# Schematic.net
KiCad netlist of a schematic drawn in EAGLE
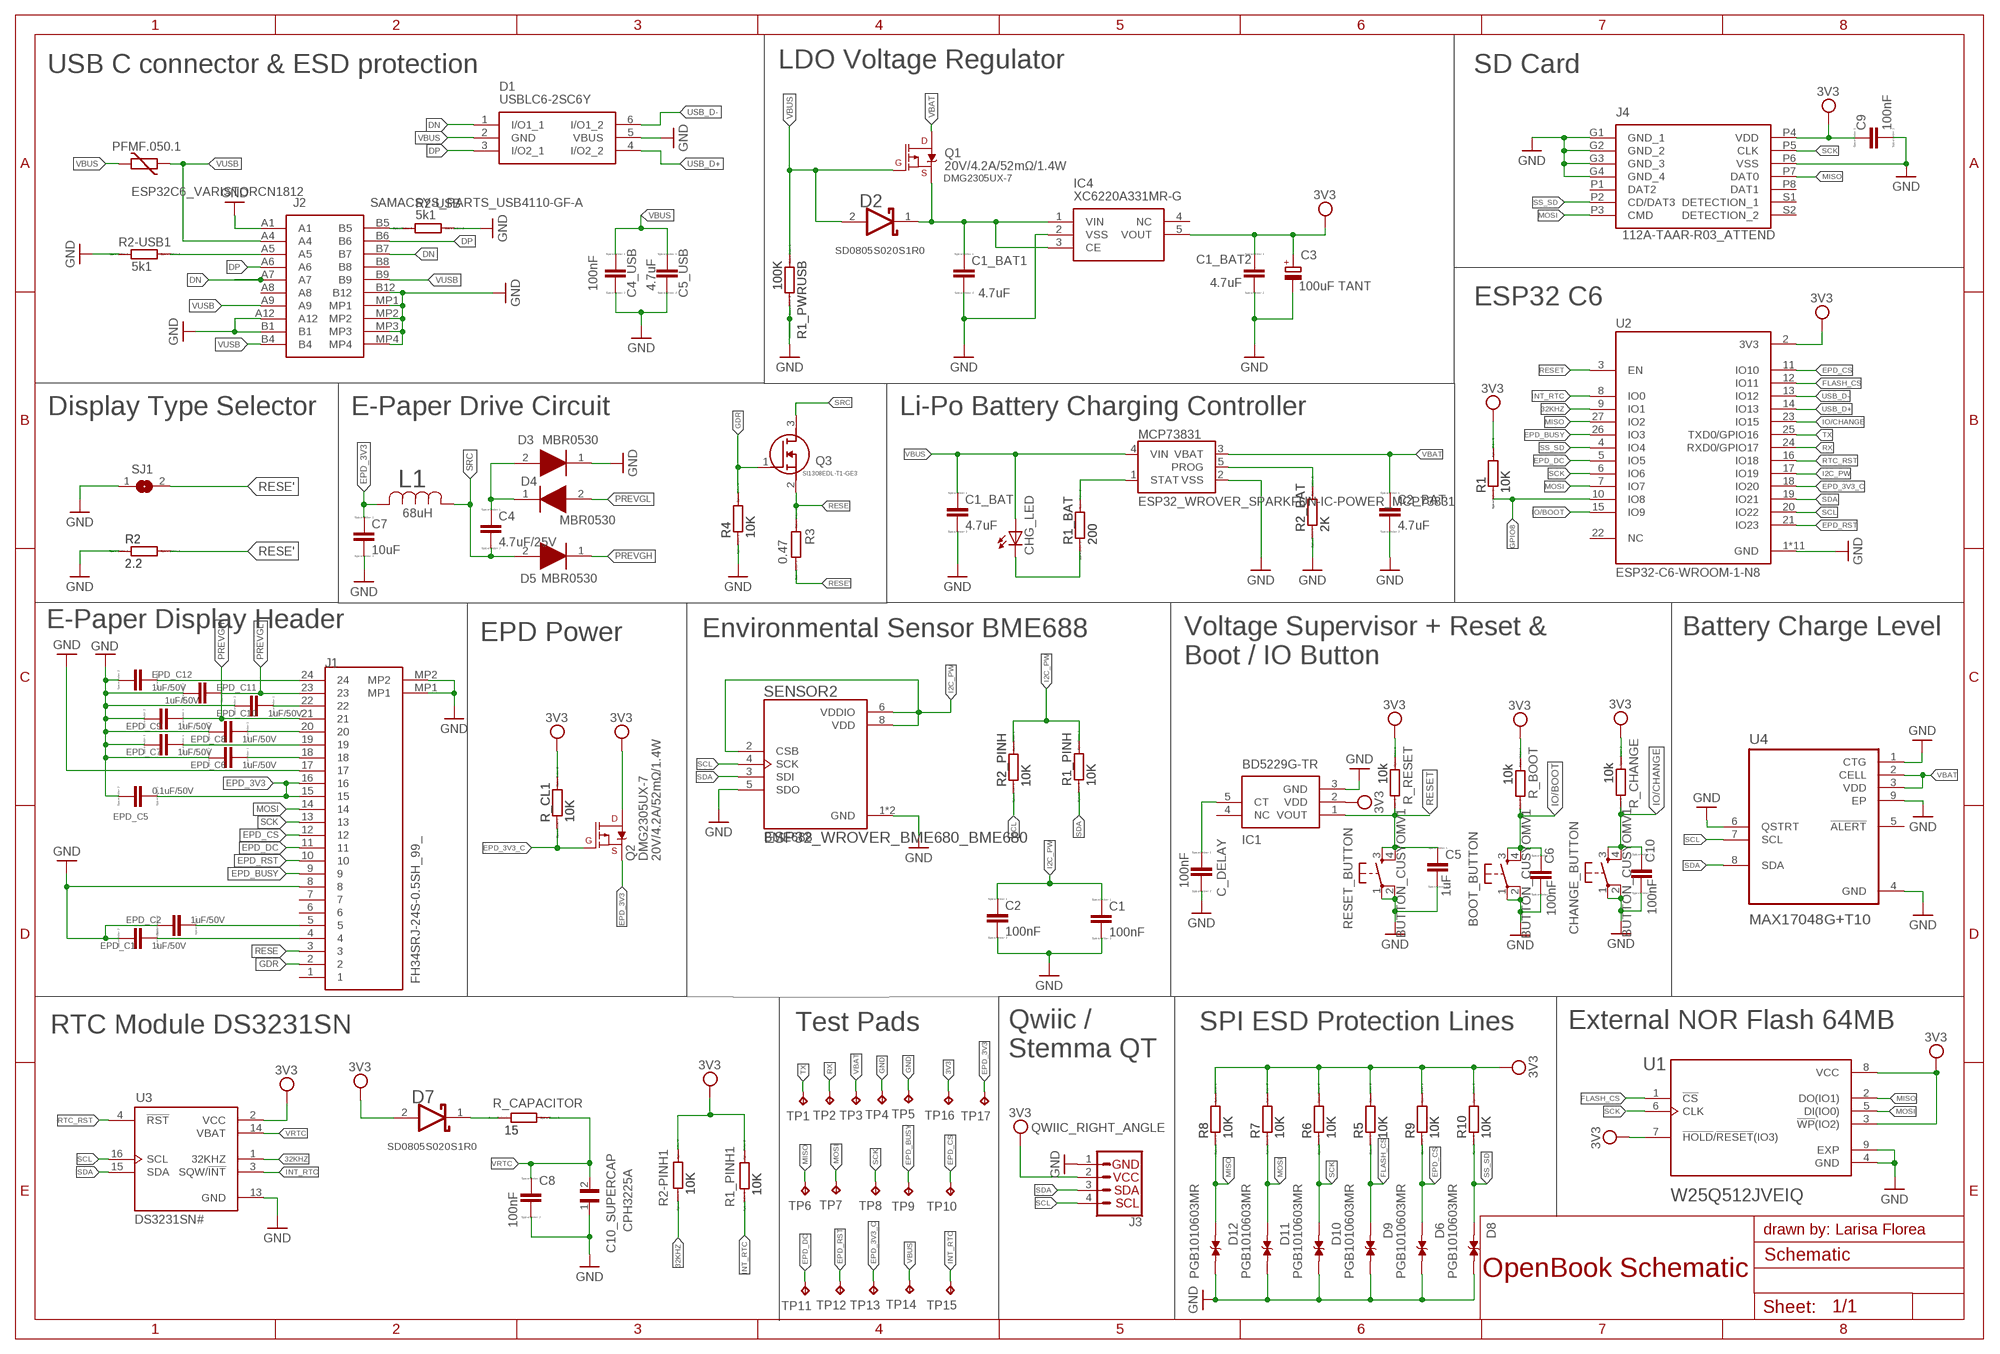
[diagram p0: schematic, sheet 1]

(export (version "E")
  (design (tool "Eeschema 10.0.6"))
  (components
    (comp (ref "BOOT_BUTTON")
      (value "BUTTON_CUSYOMV1")
      (footprint "eagle-import:MYBUTTON")
      (libsource (lib "eagle-import") (part "BUTTON_CUSYOMV1"))
    )
    (comp (ref "C1")
      (value "100nF")
      (footprint "eagle-import:EAGLE-LTSPICE_C0402")
      (libsource (lib "eagle-import") (part "EAGLE-LTSPICE_CC0402"))
    )
    (comp (ref "C1_BAT")
      (value "4.7uF")
      (footprint "eagle-import:EAGLE-LTSPICE_C0402")
      (libsource (lib "eagle-import") (part "EAGLE-LTSPICE_CC0402"))
    )
    (comp (ref "C1_BAT1")
      (value "4.7uF")
      (footprint "eagle-import:ESP32_WROVER_EAGLE-LTSPICE_C0402")
      (libsource (lib "eagle-import") (part "ESP32_WROVER_EAGLE-LTSPICE_CC0402"))
    )
    (comp (ref "C1_BAT2")
      (value "4.7uF")
      (footprint "eagle-import:ESP32_WROVER_EAGLE-LTSPICE_C0402")
      (libsource (lib "eagle-import") (part "ESP32_WROVER_EAGLE-LTSPICE_CC0402"))
    )
    (comp (ref "C2")
      (value "100nF")
      (footprint "eagle-import:EAGLE-LTSPICE_C0402")
      (libsource (lib "eagle-import") (part "EAGLE-LTSPICE_CC0402"))
    )
    (comp (ref "C2_BAT")
      (value "4.7uF")
      (footprint "eagle-import:EAGLE-LTSPICE_C0402")
      (libsource (lib "eagle-import") (part "EAGLE-LTSPICE_CC0402"))
    )
    (comp (ref "C3")
      (value "100uF TANT")
      (footprint "eagle-import:RCL_CT3528")
      (libsource (lib "eagle-import") (part "RCL_CPOL-EUCT3528"))
    )
    (comp (ref "C4")
      (value "4.7uF/25V")
      (footprint "eagle-import:ESP32_WROVER_EAGLE-LTSPICE_C0402")
      (libsource (lib "eagle-import") (part "ESP32_WROVER_EAGLE-LTSPICE_CC0402"))
    )
    (comp (ref "C4_USB")
      (value "100nF")
      (footprint "eagle-import:ESP32_WROVER_EAGLE-LTSPICE_C0402")
      (libsource (lib "eagle-import") (part "ESP32_WROVER_EAGLE-LTSPICE_CC0402"))
    )
    (comp (ref "C5")
      (value "1uF")
      (footprint "eagle-import:EAGLE-LTSPICE_C0402")
      (libsource (lib "eagle-import") (part "EAGLE-LTSPICE_CC0402"))
    )
    (comp (ref "C5_USB")
      (value "4.7uF")
      (footprint "eagle-import:ESP32_WROVER_EAGLE-LTSPICE_C0402")
      (libsource (lib "eagle-import") (part "ESP32_WROVER_EAGLE-LTSPICE_CC0402"))
    )
    (comp (ref "C6")
      (value "100nF")
      (footprint "eagle-import:EAGLE-LTSPICE_C0402")
      (libsource (lib "eagle-import") (part "EAGLE-LTSPICE_CC0402"))
    )
    (comp (ref "C7")
      (value "10uF")
      (footprint "eagle-import:ESP32_WROVER_EAGLE-LTSPICE_C0402")
      (libsource (lib "eagle-import") (part "ESP32_WROVER_EAGLE-LTSPICE_CC0402"))
    )
    (comp (ref "C8")
      (value "100nF")
      (footprint "eagle-import:EAGLE-LTSPICE_C0402")
      (libsource (lib "eagle-import") (part "EAGLE-LTSPICE_CC0402"))
    )
    (comp (ref "C9")
      (value "100nF")
      (footprint "eagle-import:EAGLE-LTSPICE_C0402")
      (libsource (lib "eagle-import") (part "EAGLE-LTSPICE_CC0402"))
    )
    (comp (ref "C10")
      (value "100nF")
      (footprint "eagle-import:EAGLE-LTSPICE_C0402")
      (libsource (lib "eagle-import") (part "EAGLE-LTSPICE_CC0402"))
    )
    (comp (ref "C10_SUPERCAP")
      (value "CPH3225A")
      (footprint "eagle-import:CAPCP3225X100N")
      (fields (field (name "MF") "Seiko Instruments"))
      (libsource (lib "eagle-import") (part "CPH3225A"))
    )
    (comp (ref "CHANGE_BUTTON")
      (value "BUTTON_CUSYOMV1")
      (footprint "eagle-import:MYBUTTON")
      (libsource (lib "eagle-import") (part "BUTTON_CUSYOMV1"))
    )
    (comp (ref "CHG_LED")
      (value "ADAFRUIT_LEDCHIP-LED0603")
      (footprint "eagle-import:ADAFRUIT_CHIP-LED0603")
      (libsource (lib "eagle-import") (part "ADAFRUIT_LEDCHIP-LED0603"))
    )
    (comp (ref "C_DELAY")
      (value "100nF")
      (footprint "eagle-import:EAGLE-LTSPICE_C0402")
      (libsource (lib "eagle-import") (part "EAGLE-LTSPICE_CC0402"))
    )
    (comp (ref "D1")
      (value "USBLC6-2SC6Y")
      (footprint "eagle-import:SOT95P280X145-6N")
      (fields (field (name "MF") "STMicroelectronics"))
      (libsource (lib "eagle-import") (part "USBLC6-2SC6Y"))
    )
    (comp (ref "D2")
      (value "ESP32_WROVER_AVX---SD0805S020S1R0_AVX_SD0805S020S1R0_0_0AVX_SD0805S020S1R0_0_0")
      (footprint "eagle-import:ESP32_WROVER_AVX---SD0805S020S1R0_AVX_SD0805S020S1R0_0")
      (fields
        (field (name "DIGIKEY_PART_NUMBER") "478-7800-1-ND")
        (field (name "MF") "AVX")
        (field (name "MOUSER_PART_NUMBER") "581-SD0805S020S1R0")
      )
      (libsource (lib "eagle-import") (part "ESP32_WROVER_AVX---SD0805S020S1R0_AVX_SD0805S020S1R0_0_0AVX_SD0805S020S1R0_0_0"))
    )
    (comp (ref "D3")
      (value "MBR0530")
      (footprint "eagle-import:SOD3716X135N")
      (fields (field (name "MF") "ON Semiconductor"))
      (libsource (lib "eagle-import") (part "MBR0530"))
    )
    (comp (ref "D4")
      (value "MBR0530")
      (footprint "eagle-import:SOD3716X135N")
      (fields (field (name "MF") "ON Semiconductor"))
      (libsource (lib "eagle-import") (part "MBR0530"))
    )
    (comp (ref "D5")
      (value "MBR0530")
      (footprint "eagle-import:SOD3716X135N")
      (fields (field (name "MF") "ON Semiconductor"))
      (libsource (lib "eagle-import") (part "MBR0530"))
    )
    (comp (ref "D6")
      (value "PGB1010603MR")
      (footprint "eagle-import:DIOC1608X36N")
      (fields (field (name "MF") "Littelfuse Inc."))
      (libsource (lib "eagle-import") (part "PGB1010603MR"))
    )
    (comp (ref "D7")
      (value "ESP32_WROVER_AVX---SD0805S020S1R0_AVX_SD0805S020S1R0_0_0AVX_SD0805S020S1R0_0_0")
      (footprint "eagle-import:ESP32_WROVER_AVX---SD0805S020S1R0_AVX_SD0805S020S1R0_0")
      (fields
        (field (name "DIGIKEY_PART_NUMBER") "478-7800-1-ND")
        (field (name "MF") "AVX")
        (field (name "MOUSER_PART_NUMBER") "581-SD0805S020S1R0")
      )
      (libsource (lib "eagle-import") (part "ESP32_WROVER_AVX---SD0805S020S1R0_AVX_SD0805S020S1R0_0_0AVX_SD0805S020S1R0_0_0"))
    )
    (comp (ref "D8")
      (value "PGB1010603MR")
      (footprint "eagle-import:DIOC1608X36N")
      (fields (field (name "MF") "Littelfuse Inc."))
      (libsource (lib "eagle-import") (part "PGB1010603MR"))
    )
    (comp (ref "D9")
      (value "PGB1010603MR")
      (footprint "eagle-import:DIOC1608X36N")
      (fields (field (name "MF") "Littelfuse Inc."))
      (libsource (lib "eagle-import") (part "PGB1010603MR"))
    )
    (comp (ref "D10")
      (value "PGB1010603MR")
      (footprint "eagle-import:DIOC1608X36N")
      (fields (field (name "MF") "Littelfuse Inc."))
      (libsource (lib "eagle-import") (part "PGB1010603MR"))
    )
    (comp (ref "D11")
      (value "PGB1010603MR")
      (footprint "eagle-import:DIOC1608X36N")
      (fields (field (name "MF") "Littelfuse Inc."))
      (libsource (lib "eagle-import") (part "PGB1010603MR"))
    )
    (comp (ref "D12")
      (value "PGB1010603MR")
      (footprint "eagle-import:DIOC1608X36N")
      (fields (field (name "MF") "Littelfuse Inc."))
      (libsource (lib "eagle-import") (part "PGB1010603MR"))
    )
    (comp (ref "EPD_C1")
      (value "1uF/50V")
      (footprint "eagle-import:ESP32_WROVER_EAGLE-LTSPICE_C0402")
      (libsource (lib "eagle-import") (part "DeskAssistant v19 v1_vf.GPlzlSHfQFaX3NeFr78fQQ_ESP32_WROVER_EAGLE-LTSPICE_CC0402"))
    )
    (comp (ref "EPD_C2")
      (value "1uF/50V")
      (footprint "eagle-import:ESP32_WROVER_EAGLE-LTSPICE_C0402")
      (libsource (lib "eagle-import") (part "DeskAssistant v19 v1_vf.GPlzlSHfQFaX3NeFr78fQQ_ESP32_WROVER_EAGLE-LTSPICE_CC0402"))
    )
    (comp (ref "EPD_C5")
      (value "0.1uF/50V")
      (footprint "eagle-import:ESP32_WROVER_EAGLE-LTSPICE_C0402")
      (libsource (lib "eagle-import") (part "DeskAssistant v19 v1_vf.GPlzlSHfQFaX3NeFr78fQQ_ESP32_WROVER_EAGLE-LTSPICE_CC0402"))
    )
    (comp (ref "EPD_C6")
      (value "1uF/50V")
      (footprint "eagle-import:ESP32_WROVER_EAGLE-LTSPICE_C0402")
      (libsource (lib "eagle-import") (part "DeskAssistant v19 v1_vf.GPlzlSHfQFaX3NeFr78fQQ_ESP32_WROVER_EAGLE-LTSPICE_CC0402"))
    )
    (comp (ref "EPD_C7")
      (value "1uF/50V")
      (footprint "eagle-import:ESP32_WROVER_EAGLE-LTSPICE_C0402")
      (libsource (lib "eagle-import") (part "DeskAssistant v19 v1_vf.GPlzlSHfQFaX3NeFr78fQQ_ESP32_WROVER_EAGLE-LTSPICE_CC0402"))
    )
    (comp (ref "EPD_C8")
      (value "1uF/50V")
      (footprint "eagle-import:ESP32_WROVER_EAGLE-LTSPICE_C0402")
      (libsource (lib "eagle-import") (part "DeskAssistant v19 v1_vf.GPlzlSHfQFaX3NeFr78fQQ_ESP32_WROVER_EAGLE-LTSPICE_CC0402"))
    )
    (comp (ref "EPD_C9")
      (value "1uF/50V")
      (footprint "eagle-import:ESP32_WROVER_EAGLE-LTSPICE_C0402")
      (libsource (lib "eagle-import") (part "DeskAssistant v19 v1_vf.GPlzlSHfQFaX3NeFr78fQQ_ESP32_WROVER_EAGLE-LTSPICE_CC0402"))
    )
    (comp (ref "EPD_C10")
      (value "1uF/50V")
      (footprint "eagle-import:ESP32_WROVER_EAGLE-LTSPICE_C0402")
      (libsource (lib "eagle-import") (part "DeskAssistant v19 v1_vf.GPlzlSHfQFaX3NeFr78fQQ_ESP32_WROVER_EAGLE-LTSPICE_CC0402"))
    )
    (comp (ref "EPD_C11")
      (value "1uF/50V")
      (footprint "eagle-import:ESP32_WROVER_EAGLE-LTSPICE_C0402")
      (libsource (lib "eagle-import") (part "DeskAssistant v19 v1_vf.GPlzlSHfQFaX3NeFr78fQQ_ESP32_WROVER_EAGLE-LTSPICE_CC0402"))
    )
    (comp (ref "EPD_C12")
      (value "1uF/50V")
      (footprint "eagle-import:ESP32_WROVER_EAGLE-LTSPICE_C0402")
      (libsource (lib "eagle-import") (part "DeskAssistant v19 v1_vf.GPlzlSHfQFaX3NeFr78fQQ_ESP32_WROVER_EAGLE-LTSPICE_CC0402"))
    )
    (comp (ref "IC1")
      (value "BD5229G-TR")
      (footprint "eagle-import:SOT95P280X125-5N")
      (fields (field (name "MOUSER_PART_NUMBER") "755-BD5229G-TR"))
      (libsource (lib "eagle-import") (part "BD5229G-TR"))
    )
    (comp (ref "IC4")
      (value "XC6220A331MR-G")
      (footprint "eagle-import:SOT95P280X120-5N")
      (fields (field (name "MOUSER_PART_NUMBER") "865-XC6220A331MR-G"))
      (libsource (lib "eagle-import") (part "XC6220A331MR-G"))
    )
    (comp (ref "J1")
      (value "FH34SRJ-24S-0.5SH_99_")
      (footprint "eagle-import:FH34SRJ24S05SH99")
      (fields
        (field (name "MANUFACTURER_PART_NUMBER") "FH34SRJ-24S-0.5SH(99)")
        (field (name "MOUSER_PART_NUMBER") "798-FH34SRJ24S05SH99")
      )
      (libsource (lib "eagle-import") (part "FH34SRJ-24S-0.5SH_99_"))
    )
    (comp (ref "J2")
      (value "SAMACSYS_PARTS_USB4110-GF-A")
      (footprint "eagle-import:SAMACSYS_PARTS_USB4110GFA")
      (fields
        (field (name "MANUFACTURER_PART_NUMBER") "USB4110-GF-A")
        (field (name "MOUSER_PART_NUMBER") "640-USB4110-GF-A")
      )
      (libsource (lib "eagle-import") (part "SAMACSYS_PARTS_USB4110-GF-A"))
    )
    (comp (ref "J3")
      (value "QWIIC_RIGHT_ANGLE")
      (footprint "eagle-import:JST04_1MM_RA")
      (libsource (lib "eagle-import") (part "QWIIC_CONNECTORJS-1MM"))
    )
    (comp (ref "J4")
      (value "112A-TAAR-R03_ATTEND")
      (footprint "eagle-import:112ATAARR03ATTEND")
      (fields (field (name "MANUFACTURER_PART_NUMBER") "112A-TAAR-R03 ATTEND"))
      (libsource (lib "eagle-import") (part "112A-TAAR-R03_ATTEND"))
    )
    (comp (ref "L1")
      (value "744043680IND_4828-WE-TPC_WRE")
      (footprint "eagle-import:IND_4828-WE-TPC_WRE")
      (fields
        (field (name "MANUFACTURER_PART_NUMBER") "744043680")
        (field (name "68UH") "68uH")
        (field (name "COPYRIGHT") "Copyright (C) 2024 Ultra Librarian. All rights reserved.")
      )
      (libsource (lib "eagle-import") (part "744043680IND_4828-WE-TPC_WRE"))
    )
    (comp (ref "MCP73831")
      (value "ESP32_WROVER_SPARKFUN-IC-POWER_MCP73831")
      (footprint "eagle-import:ESP32_WROVER_SPARKFUN-IC-POWER_SOT23-5")
      (libsource (lib "eagle-import") (part "ESP32_WROVER_SPARKFUN-IC-POWER_MCP73831"))
    )
    (comp (ref "PFMF.050.1")
      (value "ESP32C6_VARISTORCN1812")
      (footprint "eagle-import:ESP32C6_VARISTOR_CT_CN1812")
      (libsource (lib "eagle-import") (part "ESP32C6_VARISTORCN1812"))
    )
    (comp (ref "Q1")
      (value "20V/4.2A/52mΩ/1.4W")
      (footprint "eagle-import:ESP32_WROVER_SPARKFUN-DISCRETESEMI_SOT23-3")
      (libsource (lib "eagle-import") (part "ESP32_WROVER_SPARKFUN-DISCRETESEMI_MOSFET_PCH-DMG2305UX-7"))
    )
    (comp (ref "Q2")
      (value "20V/4.2A/52mΩ/1.4W")
      (footprint "eagle-import:ESP32_WROVER_SPARKFUN-DISCRETESEMI_SOT23-3")
      (libsource (lib "eagle-import") (part "ESP32_WROVER_SPARKFUN-DISCRETESEMI_MOSFET_PCH-DMG2305UX-7"))
    )
    (comp (ref "Q3")
      (value "SI1308EDL-T1-GE3")
      (footprint "eagle-import:SOT65P210X110-3N")
      (fields (field (name "MF") "Vishay Siliconix"))
      (libsource (lib "eagle-import") (part "SI1308EDL-T1-GE3"))
    )
    (comp (ref "R1")
      (value "10K")
      (footprint "eagle-import:ESP32_WROVER_EAGLE-LTSPICE_R0402")
      (libsource (lib "eagle-import") (part "ESP32_WROVER_EAGLE-LTSPICE_RR0402"))
    )
    (comp (ref "R1_BAT")
      (value "200")
      (footprint "eagle-import:ESP32_WROVER_EAGLE-LTSPICE_R0402")
      (libsource (lib "eagle-import") (part "ESP32_WROVER_EAGLE-LTSPICE_RR0402"))
    )
    (comp (ref "R1_PINH")
      (value "10K")
      (footprint "eagle-import:ESP32_WROVER_EAGLE-LTSPICE_R0402")
      (libsource (lib "eagle-import") (part "ESP32_WROVER_EAGLE-LTSPICE_RR0402"))
    )
    (comp (ref "R1_PINH1")
      (value "10K")
      (footprint "eagle-import:ESP32_WROVER_EAGLE-LTSPICE_R0402")
      (libsource (lib "eagle-import") (part "ESP32_WROVER_EAGLE-LTSPICE_RR0402"))
    )
    (comp (ref "R1_PWRUSB")
      (value "100K")
      (footprint "eagle-import:ESP32_WROVER_EAGLE-LTSPICE_R0402")
      (libsource (lib "eagle-import") (part "ESP32_WROVER_EAGLE-LTSPICE_RR0402"))
    )
    (comp (ref "R2")
      (value "2.2")
      (footprint "eagle-import:ESP32_WROVER_EAGLE-LTSPICE_R0402")
      (libsource (lib "eagle-import") (part "ESP32_WROVER_EAGLE-LTSPICE_RR0402"))
    )
    (comp (ref "R2-PINH1")
      (value "10K")
      (footprint "eagle-import:ESP32_WROVER_EAGLE-LTSPICE_R0402")
      (libsource (lib "eagle-import") (part "ESP32_WROVER_EAGLE-LTSPICE_RR0402"))
    )
    (comp (ref "R2-USB")
      (value "5k1")
      (footprint "eagle-import:ESP32_WROVER_EAGLE-LTSPICE_R0402")
      (libsource (lib "eagle-import") (part "ESP32_WROVER_EAGLE-LTSPICE_RR0402"))
    )
    (comp (ref "R2-USB1")
      (value "5k1")
      (footprint "eagle-import:ESP32_WROVER_EAGLE-LTSPICE_R0402")
      (libsource (lib "eagle-import") (part "ESP32_WROVER_EAGLE-LTSPICE_RR0402"))
    )
    (comp (ref "R2_BAT")
      (value "2K")
      (footprint "eagle-import:ESP32_WROVER_EAGLE-LTSPICE_R0402")
      (libsource (lib "eagle-import") (part "ESP32_WROVER_EAGLE-LTSPICE_RR0402"))
    )
    (comp (ref "R2_PINH")
      (value "10K")
      (footprint "eagle-import:ESP32_WROVER_EAGLE-LTSPICE_R0402")
      (libsource (lib "eagle-import") (part "ESP32_WROVER_EAGLE-LTSPICE_RR0402"))
    )
    (comp (ref "R3")
      (value "0.47")
      (footprint "eagle-import:ESP32_WROVER_EAGLE-LTSPICE_R0402")
      (libsource (lib "eagle-import") (part "ESP32_WROVER_EAGLE-LTSPICE_RR0402"))
    )
    (comp (ref "R4")
      (value "10K")
      (footprint "eagle-import:ESP32_WROVER_EAGLE-LTSPICE_R0402")
      (libsource (lib "eagle-import") (part "ESP32_WROVER_EAGLE-LTSPICE_RR0402"))
    )
    (comp (ref "R5")
      (value "10K")
      (footprint "eagle-import:ESP32_WROVER_EAGLE-LTSPICE_R0402")
      (libsource (lib "eagle-import") (part "DeskAssistant v19 v1_vf.GPlzlSHfQFaX3NeFr78fQQ_ESP32_WROVER_EAGLE-LTSPICE_RR0402"))
    )
    (comp (ref "R6")
      (value "10K")
      (footprint "eagle-import:ESP32_WROVER_EAGLE-LTSPICE_R0402")
      (libsource (lib "eagle-import") (part "DeskAssistant v19 v1_vf.GPlzlSHfQFaX3NeFr78fQQ_ESP32_WROVER_EAGLE-LTSPICE_RR0402"))
    )
    (comp (ref "R7")
      (value "10K")
      (footprint "eagle-import:ESP32_WROVER_EAGLE-LTSPICE_R0402")
      (libsource (lib "eagle-import") (part "DeskAssistant v19 v1_vf.GPlzlSHfQFaX3NeFr78fQQ_ESP32_WROVER_EAGLE-LTSPICE_RR0402"))
    )
    (comp (ref "R8")
      (value "10K")
      (footprint "eagle-import:ESP32_WROVER_EAGLE-LTSPICE_R0402")
      (libsource (lib "eagle-import") (part "DeskAssistant v19 v1_vf.GPlzlSHfQFaX3NeFr78fQQ_ESP32_WROVER_EAGLE-LTSPICE_RR0402"))
    )
    (comp (ref "R9")
      (value "10K")
      (footprint "eagle-import:ESP32_WROVER_EAGLE-LTSPICE_R0402")
      (libsource (lib "eagle-import") (part "DeskAssistant v19 v1_vf.GPlzlSHfQFaX3NeFr78fQQ_ESP32_WROVER_EAGLE-LTSPICE_RR0402"))
    )
    (comp (ref "R10")
      (value "10K")
      (footprint "eagle-import:ESP32_WROVER_EAGLE-LTSPICE_R0402")
      (libsource (lib "eagle-import") (part "DeskAssistant v19 v1_vf.GPlzlSHfQFaX3NeFr78fQQ_ESP32_WROVER_EAGLE-LTSPICE_RR0402"))
    )
    (comp (ref "RESET_BUTTON")
      (value "BUTTON_CUSYOMV1")
      (footprint "eagle-import:MYBUTTON")
      (libsource (lib "eagle-import") (part "BUTTON_CUSYOMV1"))
    )
    (comp (ref "R_BOOT")
      (value "10k")
      (footprint "eagle-import:ESP32_WROVER_EAGLE-LTSPICE_R0402")
      (libsource (lib "eagle-import") (part "ESP32_WROVER_EAGLE-LTSPICE_RR0402"))
    )
    (comp (ref "R_CAPACITOR")
      (value "15")
      (footprint "eagle-import:ESP32_WROVER_EAGLE-LTSPICE_R0402")
      (libsource (lib "eagle-import") (part "ESP32_WROVER_EAGLE-LTSPICE_RR0402"))
    )
    (comp (ref "R_CHANGE")
      (value "10k")
      (footprint "eagle-import:ESP32_WROVER_EAGLE-LTSPICE_R0402")
      (libsource (lib "eagle-import") (part "ESP32_WROVER_EAGLE-LTSPICE_RR0402"))
    )
    (comp (ref "R_CL1")
      (value "10K")
      (footprint "eagle-import:ESP32_WROVER_EAGLE-LTSPICE_R0402")
      (libsource (lib "eagle-import") (part "ESP32_WROVER_EAGLE-LTSPICE_RR0402"))
    )
    (comp (ref "R_RESET")
      (value "10k")
      (footprint "eagle-import:ESP32_WROVER_EAGLE-LTSPICE_R0402")
      (libsource (lib "eagle-import") (part "ESP32_WROVER_EAGLE-LTSPICE_RR0402"))
    )
    (comp (ref "SENSOR2")
      (value "ESP32_WROVER_BME680_BME680")
      (footprint "eagle-import:ESP32_WROVER_BME680_PSON80P300X300X100-8N")
      (fields (field (name "MF") "Bosch Sensortec") (field (name "MP") "BME680"))
      (libsource (lib "eagle-import") (part "ESP32_WROVER_BME680_BME680"))
    )
    (comp (ref "SJ1") (value "SJ") (footprint "eagle-import:SJ") (libsource (lib "eagle-import") (part "SJ")))
    (comp (ref "TP1")
      (value "TPTP20R")
      (footprint "eagle-import:TP20R")
      (libsource (lib "eagle-import") (part "TPTP20R"))
    )
    (comp (ref "TP2")
      (value "TPTP20R")
      (footprint "eagle-import:TP20R")
      (libsource (lib "eagle-import") (part "TPTP20R"))
    )
    (comp (ref "TP3")
      (value "TPTP20R")
      (footprint "eagle-import:TP20R")
      (libsource (lib "eagle-import") (part "TPTP20R"))
    )
    (comp (ref "TP4")
      (value "TPTP20R")
      (footprint "eagle-import:TP20R")
      (libsource (lib "eagle-import") (part "TPTP20R"))
    )
    (comp (ref "TP5")
      (value "TPTP20R")
      (footprint "eagle-import:TP20R")
      (libsource (lib "eagle-import") (part "TPTP20R"))
    )
    (comp (ref "TP6")
      (value "TPTP20R")
      (footprint "eagle-import:TP20R")
      (libsource (lib "eagle-import") (part "TPTP20R"))
    )
    (comp (ref "TP7")
      (value "TPTP20R")
      (footprint "eagle-import:TP20R")
      (libsource (lib "eagle-import") (part "TPTP20R"))
    )
    (comp (ref "TP8")
      (value "TPTP20R")
      (footprint "eagle-import:TP20R")
      (libsource (lib "eagle-import") (part "TPTP20R"))
    )
    (comp (ref "TP9")
      (value "TPTP20R")
      (footprint "eagle-import:TP20R")
      (libsource (lib "eagle-import") (part "TPTP20R"))
    )
    (comp (ref "TP10")
      (value "TPTP20R")
      (footprint "eagle-import:TP20R")
      (libsource (lib "eagle-import") (part "TPTP20R"))
    )
    (comp (ref "TP11")
      (value "TPTP20R")
      (footprint "eagle-import:TP20R")
      (libsource (lib "eagle-import") (part "TPTP20R"))
    )
    (comp (ref "TP12")
      (value "TPTP20R")
      (footprint "eagle-import:TP20R")
      (libsource (lib "eagle-import") (part "TPTP20R"))
    )
    (comp (ref "TP13")
      (value "TPTP20R")
      (footprint "eagle-import:TP20R")
      (libsource (lib "eagle-import") (part "TPTP20R"))
    )
    (comp (ref "TP14")
      (value "TPTP20R")
      (footprint "eagle-import:TP20R")
      (libsource (lib "eagle-import") (part "TPTP20R"))
    )
    (comp (ref "TP15")
      (value "TPTP20R")
      (footprint "eagle-import:TP20R")
      (libsource (lib "eagle-import") (part "TPTP20R"))
    )
    (comp (ref "TP16")
      (value "TPTP20R")
      (footprint "eagle-import:TP20R")
      (libsource (lib "eagle-import") (part "TPTP20R"))
    )
    (comp (ref "TP17")
      (value "TPTP20R")
      (footprint "eagle-import:TP20R")
      (libsource (lib "eagle-import") (part "TPTP20R"))
    )
    (comp (ref "U1")
      (value "W25Q512JVEIQ")
      (footprint "eagle-import:SON127P600X800X80-9N")
      (fields (field (name "MF") "Winbond Electronics"))
      (libsource (lib "eagle-import") (part "W25Q512JVEIQ"))
    )
    (comp (ref "U2")
      (value "ESP32-C6-WROOM-1-N8")
      (footprint "eagle-import:XCVR_ESP32-C6-WROOM-1-N8")
      (fields (field (name "MF") "Espressif Systems"))
      (libsource (lib "eagle-import") (part "ESP32-C6-WROOM-1-N8"))
    )
    (comp (ref "U3")
      (value "DS3231SN#")
      (footprint "eagle-import:SOIC127P1032X265-16N")
      (fields (field (name "MF") "Analog Devices"))
      (libsource (lib "eagle-import") (part "DS3231SN#"))
    )
    (comp (ref "U4")
      (value "MAX17048G+T10")
      (footprint "eagle-import:SON50P200X200X80-9N")
      (fields (field (name "MF") "Analog Devices"))
      (libsource (lib "eagle-import") (part "MAX17048G+T10"))
    )
  )
  (nets
    (net (code "1") (name "3V3") (class "Default")
      (node (ref "C1_BAT2") (pin "1") (pinfunction "1_1") (pintype "passive"))
      (node (ref "C3") (pin "+") (pinfunction "+_+") (pintype "passive"))
      (node (ref "C9") (pin "1") (pinfunction "1_1") (pintype "passive"))
      (node (ref "D7") (pin "2") (pinfunction "ANODE_2") (pintype "bidirectional"))
      (node (ref "IC1") (pin "2") (pinfunction "VDD_2") (pintype "bidirectional"))
      (node (ref "IC4") (pin "5") (pinfunction "VOUT_5") (pintype "bidirectional"))
      (node (ref "J3") (pin "2") (pinfunction "2_2") (pintype "power_in"))
      (node (ref "J4") (pin "P4") (pinfunction "VDD_P4") (pintype "bidirectional"))
      (node (ref "Q2") (pin "3") (pinfunction "D_3") (pintype "bidirectional"))
      (node (ref "R1") (pin "2") (pinfunction "2_2") (pintype "passive"))
      (node (ref "R10") (pin "2") (pinfunction "2_2") (pintype "passive"))
      (node (ref "R1_PINH1") (pin "2") (pinfunction "2_2") (pintype "passive"))
      (node (ref "R2-PINH1") (pin "2") (pinfunction "2_2") (pintype "passive"))
      (node (ref "R5") (pin "2") (pinfunction "2_2") (pintype "passive"))
      (node (ref "R6") (pin "2") (pinfunction "2_2") (pintype "passive"))
      (node (ref "R7") (pin "2") (pinfunction "2_2") (pintype "passive"))
      (node (ref "R8") (pin "2") (pinfunction "2_2") (pintype "passive"))
      (node (ref "R9") (pin "2") (pinfunction "2_2") (pintype "passive"))
      (node (ref "R_BOOT") (pin "1") (pinfunction "1_1") (pintype "passive"))
      (node (ref "R_CHANGE") (pin "1") (pinfunction "1_1") (pintype "passive"))
      (node (ref "R_CL1") (pin "2") (pinfunction "2_2") (pintype "passive"))
      (node (ref "R_RESET") (pin "1") (pinfunction "1_1") (pintype "passive"))
      (node (ref "TP16") (pin "TP") (pinfunction "TP_TP") (pintype "input"))
      (node (ref "U1") (pin "3") (pinfunction "~{WP}(IO2)_3") (pintype "bidirectional"))
      (node (ref "U1") (pin "7") (pinfunction "~{HOLD}/~{RESET}(IO3)_7") (pintype "bidirectional"))
      (node (ref "U1") (pin "8") (pinfunction "VCC_8") (pintype "power_in"))
      (node (ref "U2") (pin "2") (pinfunction "3V3_2") (pintype "power_in"))
      (node (ref "U3") (pin "2") (pinfunction "VCC_2") (pintype "power_in"))
    )
    (net (code "2") (name "32KHZ") (class "Default")
      (node (ref "R2-PINH1") (pin "1") (pinfunction "1_1") (pintype "passive"))
      (node (ref "U2") (pin "9") (pinfunction "IO1_9") (pintype "bidirectional"))
      (node (ref "U3") (pin "1") (pinfunction "32KHZ_1") (pintype "output"))
    )
    (net (code "3") (name "DN") (class "Default")
      (node (ref "D1") (pin "1") (pinfunction "I/O1_1_1") (pintype "bidirectional"))
      (node (ref "J2") (pin "A7") (pinfunction "A7_A7") (pintype "bidirectional"))
      (node (ref "J2") (pin "B7") (pinfunction "B7_B7") (pintype "bidirectional"))
    )
    (net (code "4") (name "DP") (class "Default")
      (node (ref "D1") (pin "3") (pinfunction "I/O2_1_3") (pintype "bidirectional"))
      (node (ref "J2") (pin "A6") (pinfunction "A6_A6") (pintype "bidirectional"))
      (node (ref "J2") (pin "B6") (pinfunction "B6_B6") (pintype "bidirectional"))
    )
    (net (code "5") (name "EPD_3V3") (class "Default")
      (node (ref "C7") (pin "1") (pinfunction "1_1") (pintype "passive"))
      (node (ref "EPD_C5") (pin "1") (pinfunction "1_1") (pintype "passive"))
      (node (ref "J1") (pin "15") (pinfunction "15_15") (pintype "bidirectional"))
      (node (ref "J1") (pin "16") (pinfunction "16_16") (pintype "bidirectional"))
      (node (ref "L1") (pin "2") (pinfunction "2_2") (pintype "passive"))
      (node (ref "Q2") (pin "2") (pinfunction "S_2") (pintype "bidirectional"))
      (node (ref "TP17") (pin "TP") (pinfunction "TP_TP") (pintype "input"))
    )
    (net (code "6") (name "EPD_3V3_C") (class "Default")
      (node (ref "Q2") (pin "1") (pinfunction "G_1") (pintype "bidirectional"))
      (node (ref "R_CL1") (pin "1") (pinfunction "1_1") (pintype "passive"))
      (node (ref "TP13") (pin "TP") (pinfunction "TP_TP") (pintype "input"))
      (node (ref "U2") (pin "18") (pinfunction "IO20_18") (pintype "bidirectional"))
    )
    (net (code "7") (name "EPD_BUSY") (class "Default")
      (node (ref "J1") (pin "9") (pinfunction "9_9") (pintype "bidirectional"))
      (node (ref "TP9") (pin "TP") (pinfunction "TP_TP") (pintype "input"))
      (node (ref "U2") (pin "26") (pinfunction "IO3_26") (pintype "bidirectional"))
    )
    (net (code "8") (name "EPD_CS") (class "Default")
      (node (ref "D6") (pin "1") (pinfunction "1_1") (pintype "passive"))
      (node (ref "J1") (pin "12") (pinfunction "12_12") (pintype "bidirectional"))
      (node (ref "R9") (pin "1") (pinfunction "1_1") (pintype "passive"))
      (node (ref "TP10") (pin "TP") (pinfunction "TP_TP") (pintype "input"))
      (node (ref "U2") (pin "11") (pinfunction "IO10_11") (pintype "bidirectional"))
    )
    (net (code "9") (name "EPD_DC") (class "Default")
      (node (ref "J1") (pin "11") (pinfunction "11_11") (pintype "bidirectional"))
      (node (ref "TP11") (pin "TP") (pinfunction "TP_TP") (pintype "input"))
      (node (ref "U2") (pin "5") (pinfunction "IO5_5") (pintype "bidirectional"))
    )
    (net (code "10") (name "EPD_RST") (class "Default")
      (node (ref "J1") (pin "10") (pinfunction "10_10") (pintype "bidirectional"))
      (node (ref "TP12") (pin "TP") (pinfunction "TP_TP") (pintype "input"))
      (node (ref "U2") (pin "21") (pinfunction "IO23_21") (pintype "bidirectional"))
    )
    (net (code "11") (name "FLASH_CS") (class "Default")
      (node (ref "D9") (pin "1") (pinfunction "1_1") (pintype "passive"))
      (node (ref "R5") (pin "1") (pinfunction "1_1") (pintype "passive"))
      (node (ref "U1") (pin "1") (pinfunction "~{CS}_1") (pintype "input"))
      (node (ref "U2") (pin "12") (pinfunction "IO11_12") (pintype "bidirectional"))
    )
    (net (code "12") (name "GDR") (class "Default")
      (node (ref "J1") (pin "2") (pinfunction "2_2") (pintype "bidirectional"))
      (node (ref "Q3") (pin "1") (pinfunction "G_1") (pintype "bidirectional"))
      (node (ref "R4") (pin "2") (pinfunction "2_2") (pintype "passive"))
    )
    (net (code "13") (name "GND") (class "Default")
      (node (ref "BOOT_BUTTON") (pin "1") (pinfunction "1_1") (pintype "passive"))
      (node (ref "BOOT_BUTTON") (pin "2") (pinfunction "2_2") (pintype "passive"))
      (node (ref "C1") (pin "2") (pinfunction "2_2") (pintype "passive"))
      (node (ref "C10") (pin "2") (pinfunction "2_2") (pintype "passive"))
      (node (ref "C10_SUPERCAP") (pin "1") (pinfunction "1_1") (pintype "passive"))
      (node (ref "C1_BAT") (pin "2") (pinfunction "2_2") (pintype "passive"))
      (node (ref "C1_BAT1") (pin "2") (pinfunction "2_2") (pintype "passive"))
      (node (ref "C1_BAT2") (pin "2") (pinfunction "2_2") (pintype "passive"))
      (node (ref "C2") (pin "2") (pinfunction "2_2") (pintype "passive"))
      (node (ref "C2_BAT") (pin "2") (pinfunction "2_2") (pintype "passive"))
      (node (ref "C3") (pin "-") (pinfunction "-_-") (pintype "passive"))
      (node (ref "C4_USB") (pin "2") (pinfunction "2_2") (pintype "passive"))
      (node (ref "C5") (pin "2") (pinfunction "2_2") (pintype "passive"))
      (node (ref "C5_USB") (pin "2") (pinfunction "2_2") (pintype "passive"))
      (node (ref "C6") (pin "2") (pinfunction "2_2") (pintype "passive"))
      (node (ref "C7") (pin "2") (pinfunction "2_2") (pintype "passive"))
      (node (ref "C8") (pin "2") (pinfunction "2_2") (pintype "passive"))
      (node (ref "C9") (pin "2") (pinfunction "2_2") (pintype "passive"))
      (node (ref "CHANGE_BUTTON") (pin "1") (pinfunction "1_1") (pintype "passive"))
      (node (ref "CHANGE_BUTTON") (pin "2") (pinfunction "2_2") (pintype "passive"))
      (node (ref "C_DELAY") (pin "2") (pinfunction "2_2") (pintype "passive"))
      (node (ref "D1") (pin "5") (pinfunction "VBUS_5") (pintype "bidirectional"))
      (node (ref "D10") (pin "2") (pinfunction "2_2") (pintype "passive"))
      (node (ref "D11") (pin "2") (pinfunction "2_2") (pintype "passive"))
      (node (ref "D12") (pin "2") (pinfunction "2_2") (pintype "passive"))
      (node (ref "D3") (pin "1") (pinfunction "K_1") (pintype "bidirectional"))
      (node (ref "D6") (pin "2") (pinfunction "2_2") (pintype "passive"))
      (node (ref "D8") (pin "2") (pinfunction "2_2") (pintype "passive"))
      (node (ref "D9") (pin "2") (pinfunction "2_2") (pintype "passive"))
      (node (ref "EPD_C1") (pin "2") (pinfunction "2_2") (pintype "passive"))
      (node (ref "EPD_C10") (pin "2") (pinfunction "2_2") (pintype "passive"))
      (node (ref "EPD_C11") (pin "2") (pinfunction "2_2") (pintype "passive"))
      (node (ref "EPD_C12") (pin "2") (pinfunction "2_2") (pintype "passive"))
      (node (ref "EPD_C2") (pin "2") (pinfunction "2_2") (pintype "passive"))
      (node (ref "EPD_C5") (pin "2") (pinfunction "2_2") (pintype "passive"))
      (node (ref "EPD_C6") (pin "2") (pinfunction "2_2") (pintype "passive"))
      (node (ref "EPD_C7") (pin "2") (pinfunction "2_2") (pintype "passive"))
      (node (ref "EPD_C8") (pin "2") (pinfunction "2_2") (pintype "passive"))
      (node (ref "EPD_C9") (pin "2") (pinfunction "2_2") (pintype "passive"))
      (node (ref "IC1") (pin "3") (pinfunction "GND_3") (pintype "bidirectional"))
      (node (ref "IC4") (pin "2") (pinfunction "VSS_2") (pintype "bidirectional"))
      (node (ref "J1") (pin "17") (pinfunction "17_17") (pintype "bidirectional"))
      (node (ref "J1") (pin "8") (pinfunction "8_8") (pintype "bidirectional"))
      (node (ref "J1") (pin "MP1") (pinfunction "MP1_MP1") (pintype "bidirectional"))
      (node (ref "J1") (pin "MP2") (pinfunction "MP2_MP2") (pintype "bidirectional"))
      (node (ref "J2") (pin "A1") (pinfunction "A1_A1") (pintype "bidirectional"))
      (node (ref "J2") (pin "A12") (pinfunction "A12_A12") (pintype "bidirectional"))
      (node (ref "J2") (pin "B1") (pinfunction "B1_B1") (pintype "bidirectional"))
      (node (ref "J2") (pin "B12") (pinfunction "B12_B12") (pintype "bidirectional"))
      (node (ref "J2") (pin "MP1") (pinfunction "MP1_MP1") (pintype "bidirectional"))
      (node (ref "J2") (pin "MP2") (pinfunction "MP2_MP2") (pintype "bidirectional"))
      (node (ref "J2") (pin "MP3") (pinfunction "MP3_MP3") (pintype "bidirectional"))
      (node (ref "J2") (pin "MP4") (pinfunction "MP4_MP4") (pintype "bidirectional"))
      (node (ref "J3") (pin "1") (pinfunction "1_1") (pintype "power_in"))
      (node (ref "J4") (pin "G1") (pinfunction "GND_1_G1") (pintype "bidirectional"))
      (node (ref "J4") (pin "G2") (pinfunction "GND_2_G2") (pintype "bidirectional"))
      (node (ref "J4") (pin "G3") (pinfunction "GND_3_G3") (pintype "bidirectional"))
      (node (ref "J4") (pin "G4") (pinfunction "GND_4_G4") (pintype "bidirectional"))
      (node (ref "J4") (pin "P6") (pinfunction "VSS_P6") (pintype "bidirectional"))
      (node (ref "MCP73831") (pin "2") (pinfunction "VSS_2") (pintype "power_in"))
      (node (ref "R1_PWRUSB") (pin "2") (pinfunction "2_2") (pintype "passive"))
      (node (ref "R2") (pin "1") (pinfunction "1_1") (pintype "passive"))
      (node (ref "R2-USB") (pin "2") (pinfunction "2_2") (pintype "passive"))
      (node (ref "R2-USB1") (pin "1") (pinfunction "1_1") (pintype "passive"))
      (node (ref "R2_BAT") (pin "1") (pinfunction "1_1") (pintype "passive"))
      (node (ref "R4") (pin "1") (pinfunction "1_1") (pintype "passive"))
      (node (ref "RESET_BUTTON") (pin "1") (pinfunction "1_1") (pintype "passive"))
      (node (ref "RESET_BUTTON") (pin "2") (pinfunction "2_2") (pintype "passive"))
      (node (ref "SENSOR2") (pin "1") (pinfunction "GND_1") (pintype "power_in"))
      (node (ref "SENSOR2") (pin "5") (pinfunction "SDO_5") (pintype "bidirectional"))
      (node (ref "SENSOR2") (pin "7") (pinfunction "GND_7") (pintype "power_in"))
      (node (ref "SJ1") (pin "1") (pinfunction "1_1") (pintype "passive"))
      (node (ref "TP4") (pin "TP") (pinfunction "TP_TP") (pintype "input"))
      (node (ref "TP5") (pin "TP") (pinfunction "TP_TP") (pintype "input"))
      (node (ref "U1") (pin "4") (pinfunction "GND_4") (pintype "power_in"))
      (node (ref "U1") (pin "9") (pinfunction "EXP_9") (pintype "passive"))
      (node (ref "U2") (pin "1") (pinfunction "GND_1") (pintype "power_in"))
      (node (ref "U2") (pin "28") (pinfunction "GND_28") (pintype "power_in"))
      (node (ref "U2") (pin "29_1") (pinfunction "GND_29_1") (pintype "power_in"))
      (node (ref "U2") (pin "29_2") (pinfunction "GND_29_2") (pintype "power_in"))
      (node (ref "U2") (pin "29_3") (pinfunction "GND_29_3") (pintype "power_in"))
      (node (ref "U2") (pin "29_4") (pinfunction "GND_29_4") (pintype "power_in"))
      (node (ref "U2") (pin "29_5") (pinfunction "GND_29_5") (pintype "power_in"))
      (node (ref "U2") (pin "29_6") (pinfunction "GND_29_6") (pintype "power_in"))
      (node (ref "U2") (pin "29_7") (pinfunction "GND_29_7") (pintype "power_in"))
      (node (ref "U2") (pin "29_8") (pinfunction "GND_29_8") (pintype "power_in"))
      (node (ref "U2") (pin "29_9") (pinfunction "GND_29_9") (pintype "power_in"))
      (node (ref "U3") (pin "13") (pinfunction "GND_13") (pintype "power_in"))
      (node (ref "U4") (pin "1") (pinfunction "CTG_1") (pintype "power_in"))
      (node (ref "U4") (pin "4") (pinfunction "GND_4") (pintype "power_in"))
      (node (ref "U4") (pin "6") (pinfunction "QSTRT_6") (pintype "input"))
      (node (ref "U4") (pin "9") (pinfunction "EP_9") (pintype "power_in"))
    )
    (net (code "14") (name "GPIO8") (class "Default")
      (node (ref "R1") (pin "1") (pinfunction "1_1") (pintype "passive"))
      (node (ref "U2") (pin "10") (pinfunction "IO8_10") (pintype "bidirectional"))
    )
    (net (code "15") (name "I2C_PW") (class "Default")
      (node (ref "C1") (pin "1") (pinfunction "1_1") (pintype "passive"))
      (node (ref "C2") (pin "1") (pinfunction "1_1") (pintype "passive"))
      (node (ref "R1_PINH") (pin "2") (pinfunction "2_2") (pintype "passive"))
      (node (ref "R2_PINH") (pin "2") (pinfunction "2_2") (pintype "passive"))
      (node (ref "SENSOR2") (pin "2") (pinfunction "CSB_2") (pintype "input"))
      (node (ref "SENSOR2") (pin "6") (pinfunction "VDDIO_6") (pintype "power_in"))
      (node (ref "SENSOR2") (pin "8") (pinfunction "VDD_8") (pintype "power_in"))
      (node (ref "U2") (pin "17") (pinfunction "IO19_17") (pintype "bidirectional"))
    )
    (net (code "16") (name "INT_RTC") (class "Default")
      (node (ref "R1_PINH1") (pin "1") (pinfunction "1_1") (pintype "passive"))
      (node (ref "TP15") (pin "TP") (pinfunction "TP_TP") (pintype "input"))
      (node (ref "U2") (pin "8") (pinfunction "IO0_8") (pintype "bidirectional"))
      (node (ref "U3") (pin "3") (pinfunction "SQW/~{INT}_3") (pintype "output"))
    )
    (net (code "17") (name "IO{slash}BOOT") (class "Default")
      (node (ref "BOOT_BUTTON") (pin "3") (pinfunction "3_3") (pintype "passive"))
      (node (ref "BOOT_BUTTON") (pin "4") (pinfunction "4_4") (pintype "passive"))
      (node (ref "C6") (pin "1") (pinfunction "1_1") (pintype "passive"))
      (node (ref "R_BOOT") (pin "2") (pinfunction "2_2") (pintype "passive"))
      (node (ref "U2") (pin "15") (pinfunction "IO9_15") (pintype "bidirectional"))
    )
    (net (code "18") (name "IO{slash}CHANGE") (class "Default")
      (node (ref "C10") (pin "1") (pinfunction "1_1") (pintype "passive"))
      (node (ref "CHANGE_BUTTON") (pin "3") (pinfunction "3_3") (pintype "passive"))
      (node (ref "CHANGE_BUTTON") (pin "4") (pinfunction "4_4") (pintype "passive"))
      (node (ref "R_CHANGE") (pin "2") (pinfunction "2_2") (pintype "passive"))
      (node (ref "U2") (pin "23") (pinfunction "IO15_23") (pintype "bidirectional"))
    )
    (net (code "19") (name "MISO") (class "Default")
      (node (ref "D12") (pin "1") (pinfunction "1_1") (pintype "passive"))
      (node (ref "J4") (pin "P7") (pinfunction "DAT0_P7") (pintype "bidirectional"))
      (node (ref "R8") (pin "1") (pinfunction "1_1") (pintype "passive"))
      (node (ref "TP6") (pin "TP") (pinfunction "TP_TP") (pintype "input"))
      (node (ref "U1") (pin "2") (pinfunction "DO(IO1)_2") (pintype "bidirectional"))
      (node (ref "U2") (pin "27") (pinfunction "IO2_27") (pintype "bidirectional"))
    )
    (net (code "20") (name "MOSI") (class "Default")
      (node (ref "D11") (pin "1") (pinfunction "1_1") (pintype "passive"))
      (node (ref "J1") (pin "14") (pinfunction "14_14") (pintype "bidirectional"))
      (node (ref "J4") (pin "P3") (pinfunction "CMD_P3") (pintype "bidirectional"))
      (node (ref "R7") (pin "1") (pinfunction "1_1") (pintype "passive"))
      (node (ref "TP7") (pin "TP") (pinfunction "TP_TP") (pintype "input"))
      (node (ref "U1") (pin "5") (pinfunction "DI(IO0)_5") (pintype "bidirectional"))
      (node (ref "U2") (pin "7") (pinfunction "IO7_7") (pintype "bidirectional"))
    )
    (net (code "21") (name "Net-(CHG_LED-PadC)") (class "Default")
      (node (ref "CHG_LED") (pin "C") (pinfunction "C_C") (pintype "passive"))
      (node (ref "R1_BAT") (pin "1") (pinfunction "1_1") (pintype "passive"))
    )
    (net (code "22") (name "Net-(D2-CATHODE)") (class "Default")
      (node (ref "C1_BAT1") (pin "1") (pinfunction "1_1") (pintype "passive"))
      (node (ref "D2") (pin "1") (pinfunction "CATHODE_1") (pintype "bidirectional"))
      (node (ref "IC4") (pin "1") (pinfunction "VIN_1") (pintype "bidirectional"))
      (node (ref "IC4") (pin "3") (pinfunction "CE_3") (pintype "bidirectional"))
      (node (ref "Q1") (pin "2") (pinfunction "S_2") (pintype "bidirectional"))
    )
    (net (code "23") (name "Net-(D3-A)") (class "Default")
      (node (ref "C4") (pin "1") (pinfunction "1_1") (pintype "passive"))
      (node (ref "D3") (pin "2") (pinfunction "A_2") (pintype "bidirectional"))
      (node (ref "D4") (pin "1") (pinfunction "K_1") (pintype "bidirectional"))
    )
    (net (code "24") (name "Net-(D7-CATHODE)") (class "Default")
      (node (ref "D7") (pin "1") (pinfunction "CATHODE_1") (pintype "bidirectional"))
      (node (ref "R_CAPACITOR") (pin "1") (pinfunction "1_1") (pintype "passive"))
    )
    (net (code "25") (name "Net-(EPD_C1-Pad1)") (class "Default")
      (node (ref "EPD_C1") (pin "1") (pinfunction "1_1") (pintype "passive"))
      (node (ref "J1") (pin "4") (pinfunction "4_4") (pintype "bidirectional"))
    )
    (net (code "26") (name "Net-(EPD_C2-Pad1)") (class "Default")
      (node (ref "EPD_C2") (pin "1") (pinfunction "1_1") (pintype "passive"))
      (node (ref "J1") (pin "5") (pinfunction "5_5") (pintype "bidirectional"))
    )
    (net (code "27") (name "Net-(EPD_C6-Pad1)") (class "Default")
      (node (ref "EPD_C6") (pin "1") (pinfunction "1_1") (pintype "passive"))
      (node (ref "J1") (pin "18") (pinfunction "18_18") (pintype "bidirectional"))
    )
    (net (code "28") (name "Net-(EPD_C7-Pad1)") (class "Default")
      (node (ref "EPD_C7") (pin "1") (pinfunction "1_1") (pintype "passive"))
      (node (ref "J1") (pin "19") (pinfunction "19_19") (pintype "bidirectional"))
    )
    (net (code "29") (name "Net-(EPD_C8-Pad1)") (class "Default")
      (node (ref "EPD_C8") (pin "1") (pinfunction "1_1") (pintype "passive"))
      (node (ref "J1") (pin "20") (pinfunction "20_20") (pintype "bidirectional"))
    )
    (net (code "30") (name "Net-(EPD_C10-Pad1)") (class "Default")
      (node (ref "EPD_C10") (pin "1") (pinfunction "1_1") (pintype "passive"))
      (node (ref "J1") (pin "22") (pinfunction "22_22") (pintype "bidirectional"))
    )
    (net (code "31") (name "Net-(EPD_C12-Pad1)") (class "Default")
      (node (ref "EPD_C12") (pin "1") (pinfunction "1_1") (pintype "passive"))
      (node (ref "J1") (pin "24") (pinfunction "24_24") (pintype "bidirectional"))
    )
    (net (code "32") (name "Net-(IC1-CT)") (class "Default")
      (node (ref "C_DELAY") (pin "1") (pinfunction "1_1") (pintype "passive"))
      (node (ref "IC1") (pin "5") (pinfunction "CT_5") (pintype "bidirectional"))
    )
    (net (code "33") (name "Net-(J2-PadA5)") (class "Default")
      (node (ref "J2") (pin "A5") (pinfunction "A5_A5") (pintype "bidirectional"))
      (node (ref "R2-USB1") (pin "2") (pinfunction "2_2") (pintype "passive"))
    )
    (net (code "34") (name "Net-(J2-PadB5)") (class "Default")
      (node (ref "J2") (pin "B5") (pinfunction "B5_B5") (pintype "bidirectional"))
      (node (ref "R2-USB") (pin "1") (pinfunction "1_1") (pintype "passive"))
    )
    (net (code "35") (name "Net-(MCP73831-PROG)") (class "Default")
      (node (ref "MCP73831") (pin "5") (pinfunction "PROG_5") (pintype "input"))
      (node (ref "R2_BAT") (pin "2") (pinfunction "2_2") (pintype "passive"))
    )
    (net (code "36") (name "Net-(MCP73831-STAT)") (class "Default")
      (node (ref "MCP73831") (pin "1") (pinfunction "STAT_1") (pintype "output"))
      (node (ref "R1_BAT") (pin "2") (pinfunction "2_2") (pintype "passive"))
    )
    (net (code "37") (name "PREVGH") (class "Default")
      (node (ref "D5") (pin "1") (pinfunction "K_1") (pintype "bidirectional"))
      (node (ref "EPD_C9") (pin "1") (pinfunction "1_1") (pintype "passive"))
      (node (ref "J1") (pin "21") (pinfunction "21_21") (pintype "bidirectional"))
    )
    (net (code "38") (name "PREVGL") (class "Default")
      (node (ref "D4") (pin "2") (pinfunction "A_2") (pintype "bidirectional"))
      (node (ref "EPD_C11") (pin "1") (pinfunction "1_1") (pintype "passive"))
      (node (ref "J1") (pin "23") (pinfunction "23_23") (pintype "bidirectional"))
    )
    (net (code "39") (name "RESE") (class "Default")
      (node (ref "J1") (pin "3") (pinfunction "3_3") (pintype "bidirectional"))
      (node (ref "Q3") (pin "2") (pinfunction "S_2") (pintype "bidirectional"))
      (node (ref "R3") (pin "2") (pinfunction "2_2") (pintype "passive"))
    )
    (net (code "40") (name "RESE'") (class "Default")
      (node (ref "R2") (pin "2") (pinfunction "2_2") (pintype "passive"))
      (node (ref "R3") (pin "1") (pinfunction "1_1") (pintype "passive"))
      (node (ref "SJ1") (pin "2") (pinfunction "2_2") (pintype "passive"))
    )
    (net (code "41") (name "RESET") (class "Default")
      (node (ref "C5") (pin "1") (pinfunction "1_1") (pintype "passive"))
      (node (ref "IC1") (pin "1") (pinfunction "VOUT_1") (pintype "bidirectional"))
      (node (ref "RESET_BUTTON") (pin "3") (pinfunction "3_3") (pintype "passive"))
      (node (ref "RESET_BUTTON") (pin "4") (pinfunction "4_4") (pintype "passive"))
      (node (ref "R_RESET") (pin "2") (pinfunction "2_2") (pintype "passive"))
      (node (ref "U2") (pin "3") (pinfunction "EN_3") (pintype "input"))
    )
    (net (code "42") (name "RTC_RST") (class "Default")
      (node (ref "U2") (pin "16") (pinfunction "IO18_16") (pintype "bidirectional"))
      (node (ref "U3") (pin "4") (pinfunction "~{RST}_4") (pintype "input"))
    )
    (net (code "43") (name "RX") (class "Default")
      (node (ref "TP2") (pin "TP") (pinfunction "TP_TP") (pintype "input"))
      (node (ref "U2") (pin "24") (pinfunction "RXD0/GPIO17_24") (pintype "bidirectional"))
    )
    (net (code "44") (name "SCK") (class "Default")
      (node (ref "D10") (pin "1") (pinfunction "1_1") (pintype "passive"))
      (node (ref "J1") (pin "13") (pinfunction "13_13") (pintype "bidirectional"))
      (node (ref "J4") (pin "P5") (pinfunction "CLK_P5") (pintype "bidirectional"))
      (node (ref "R6") (pin "1") (pinfunction "1_1") (pintype "passive"))
      (node (ref "TP8") (pin "TP") (pinfunction "TP_TP") (pintype "input"))
      (node (ref "U1") (pin "6") (pinfunction "CLK_6") (pintype "input"))
      (node (ref "U2") (pin "6") (pinfunction "IO6_6") (pintype "bidirectional"))
    )
    (net (code "45") (name "SCL") (class "Default")
      (node (ref "J3") (pin "4") (pinfunction "4_4") (pintype "passive"))
      (node (ref "R2_PINH") (pin "1") (pinfunction "1_1") (pintype "passive"))
      (node (ref "SENSOR2") (pin "4") (pinfunction "SCK_4") (pintype "input"))
      (node (ref "U2") (pin "20") (pinfunction "IO22_20") (pintype "bidirectional"))
      (node (ref "U3") (pin "16") (pinfunction "SCL_16") (pintype "input"))
      (node (ref "U4") (pin "7") (pinfunction "SCL_7") (pintype "input"))
    )
    (net (code "46") (name "SDA") (class "Default")
      (node (ref "J3") (pin "3") (pinfunction "3_3") (pintype "passive"))
      (node (ref "R1_PINH") (pin "1") (pinfunction "1_1") (pintype "passive"))
      (node (ref "SENSOR2") (pin "3") (pinfunction "SDI_3") (pintype "bidirectional"))
      (node (ref "U2") (pin "19") (pinfunction "IO21_19") (pintype "bidirectional"))
      (node (ref "U3") (pin "15") (pinfunction "SDA_15") (pintype "bidirectional"))
      (node (ref "U4") (pin "8") (pinfunction "SDA_8") (pintype "bidirectional"))
    )
    (net (code "47") (name "SRC") (class "Default")
      (node (ref "C4") (pin "2") (pinfunction "2_2") (pintype "passive"))
      (node (ref "D5") (pin "2") (pinfunction "A_2") (pintype "bidirectional"))
      (node (ref "L1") (pin "1") (pinfunction "1_1") (pintype "passive"))
      (node (ref "Q3") (pin "3") (pinfunction "D_3") (pintype "bidirectional"))
    )
    (net (code "48") (name "SS_SD") (class "Default")
      (node (ref "D8") (pin "1") (pinfunction "1_1") (pintype "passive"))
      (node (ref "J4") (pin "P2") (pinfunction "CD/DAT3_P2") (pintype "bidirectional"))
      (node (ref "R10") (pin "1") (pinfunction "1_1") (pintype "passive"))
      (node (ref "U2") (pin "4") (pinfunction "IO4_4") (pintype "bidirectional"))
    )
    (net (code "49") (name "TX") (class "Default")
      (node (ref "TP1") (pin "TP") (pinfunction "TP_TP") (pintype "input"))
      (node (ref "U2") (pin "25") (pinfunction "TXD0/GPIO16_25") (pintype "bidirectional"))
    )
    (net (code "50") (name "USB_D+") (class "Default")
      (node (ref "D1") (pin "4") (pinfunction "I/O2_2_4") (pintype "bidirectional"))
      (node (ref "U2") (pin "14") (pinfunction "IO13_14") (pintype "bidirectional"))
    )
    (net (code "51") (name "USB_D-") (class "Default")
      (node (ref "D1") (pin "6") (pinfunction "I/O1_2_6") (pintype "bidirectional"))
      (node (ref "U2") (pin "13") (pinfunction "IO12_13") (pintype "bidirectional"))
    )
    (net (code "52") (name "VBAT") (class "Default")
      (node (ref "C2_BAT") (pin "1") (pinfunction "1_1") (pintype "passive"))
      (node (ref "MCP73831") (pin "3") (pinfunction "VBAT_3") (pintype "power_in"))
      (node (ref "Q1") (pin "3") (pinfunction "D_3") (pintype "bidirectional"))
      (node (ref "TP3") (pin "TP") (pinfunction "TP_TP") (pintype "input"))
      (node (ref "U4") (pin "2") (pinfunction "CELL_2") (pintype "power_in"))
      (node (ref "U4") (pin "3") (pinfunction "VDD_3") (pintype "power_in"))
    )
    (net (code "53") (name "VBUS") (class "Default")
      (node (ref "C1_BAT") (pin "1") (pinfunction "1_1") (pintype "passive"))
      (node (ref "C4_USB") (pin "1") (pinfunction "1_1") (pintype "passive"))
      (node (ref "C5_USB") (pin "1") (pinfunction "1_1") (pintype "passive"))
      (node (ref "CHG_LED") (pin "A") (pinfunction "A_A") (pintype "passive"))
      (node (ref "D1") (pin "2") (pinfunction "GND_2") (pintype "bidirectional"))
      (node (ref "D2") (pin "2") (pinfunction "ANODE_2") (pintype "bidirectional"))
      (node (ref "MCP73831") (pin "4") (pinfunction "VIN_4") (pintype "power_in"))
      (node (ref "PFMF.050.1") (pin "2") (pinfunction "2_2") (pintype "passive"))
      (node (ref "Q1") (pin "1") (pinfunction "G_1") (pintype "bidirectional"))
      (node (ref "R1_PWRUSB") (pin "1") (pinfunction "1_1") (pintype "passive"))
      (node (ref "TP14") (pin "TP") (pinfunction "TP_TP") (pintype "input"))
    )
    (net (code "54") (name "VRTC") (class "Default")
      (node (ref "C10_SUPERCAP") (pin "2") (pinfunction "2_2") (pintype "passive"))
      (node (ref "C8") (pin "1") (pinfunction "1_1") (pintype "passive"))
      (node (ref "R_CAPACITOR") (pin "2") (pinfunction "2_2") (pintype "passive"))
      (node (ref "U3") (pin "14") (pinfunction "VBAT_14") (pintype "power_in"))
    )
    (net (code "55") (name "VUSB") (class "Default")
      (node (ref "J2") (pin "A4") (pinfunction "A4_A4") (pintype "bidirectional"))
      (node (ref "J2") (pin "A9") (pinfunction "A9_A9") (pintype "bidirectional"))
      (node (ref "J2") (pin "B4") (pinfunction "B4_B4") (pintype "bidirectional"))
      (node (ref "J2") (pin "B9") (pinfunction "B9_B9") (pintype "bidirectional"))
      (node (ref "PFMF.050.1") (pin "1") (pinfunction "1_1") (pintype "passive"))
    )
    (net (code "56") (name "unconnected-(IC1-NC-Pad4)") (class "Default")
      (node (ref "IC1") (pin "4") (pinfunction "NC_4") (pintype "no_connect"))
    )
    (net (code "57") (name "unconnected-(IC4-NC-Pad4)") (class "Default")
      (node (ref "IC4") (pin "4") (pinfunction "NC_4") (pintype "no_connect"))
    )
    (net (code "58") (name "unconnected-(J1-Pad1)") (class "Default")
      (node (ref "J1") (pin "1") (pinfunction "1_1") (pintype "bidirectional"))
    )
    (net (code "59") (name "unconnected-(J1-Pad6)") (class "Default")
      (node (ref "J1") (pin "6") (pinfunction "6_6") (pintype "bidirectional"))
    )
    (net (code "60") (name "unconnected-(J1-Pad7)") (class "Default")
      (node (ref "J1") (pin "7") (pinfunction "7_7") (pintype "bidirectional"))
    )
    (net (code "61") (name "unconnected-(J2-PadA8)") (class "Default")
      (node (ref "J2") (pin "A8") (pinfunction "A8_A8") (pintype "bidirectional"))
    )
    (net (code "62") (name "unconnected-(J2-PadB8)") (class "Default")
      (node (ref "J2") (pin "B8") (pinfunction "B8_B8") (pintype "bidirectional"))
    )
    (net (code "63") (name "unconnected-(J4-DAT1-PadP8)") (class "Default")
      (node (ref "J4") (pin "P8") (pinfunction "DAT1_P8") (pintype "bidirectional"))
    )
    (net (code "64") (name "unconnected-(J4-DAT2-PadP1)") (class "Default")
      (node (ref "J4") (pin "P1") (pinfunction "DAT2_P1") (pintype "bidirectional"))
    )
    (net (code "65") (name "unconnected-(J4-DETECTION_1-PadS1)") (class "Default")
      (node (ref "J4") (pin "S1") (pinfunction "DETECTION_1_S1") (pintype "bidirectional"))
    )
    (net (code "66") (name "unconnected-(J4-DETECTION_2-PadS2)") (class "Default")
      (node (ref "J4") (pin "S2") (pinfunction "DETECTION_2_S2") (pintype "bidirectional"))
    )
    (net (code "67") (name "unconnected-(U2-NC-Pad22)") (class "Default")
      (node (ref "U2") (pin "22") (pinfunction "NC_22") (pintype "no_connect"))
    )
    (net (code "68") (name "unconnected-(U4-~{ALERT}-Pad5)") (class "Default")
      (node (ref "U4") (pin "5") (pinfunction "~{ALERT}_5") (pintype "output"))
    )
  )
)
